# PCB.net
KiCad netlist of a schematic drawn in EAGLE
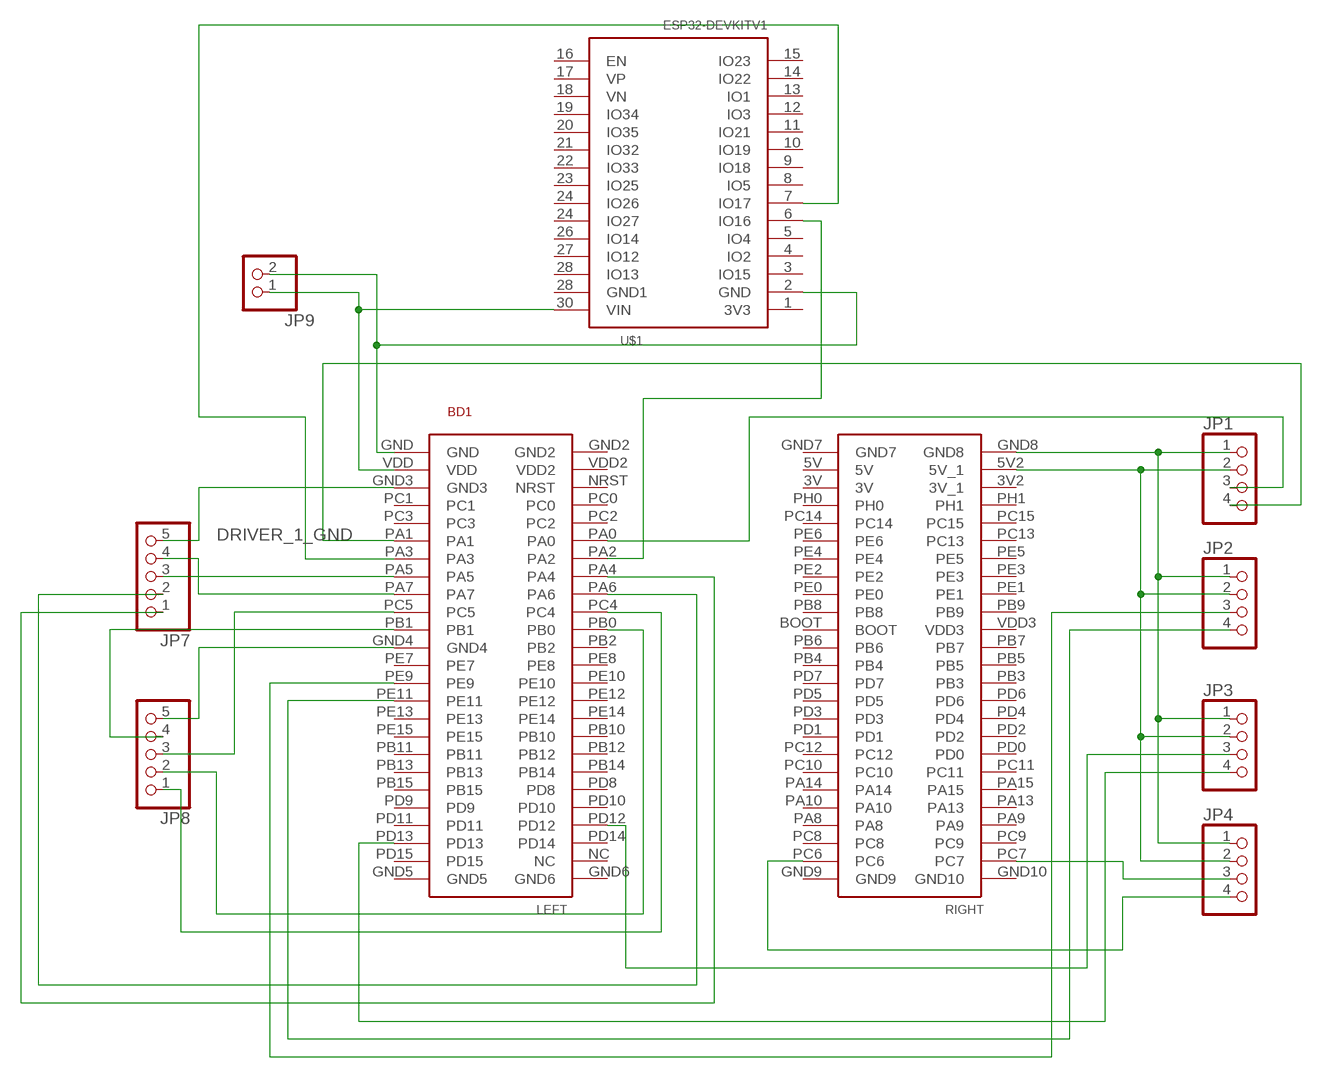
[diagram p0: schematic, sheet 1]

(export (version "E")
  (design (tool "Eeschema 10.0.6"))
  (components
    (comp (ref "BD1")
      (value "STM32F4-DISCOVERY")
      (footprint "eagle-import:STM32F407VG")
      (libsource (lib "eagle-import") (part "STM32F4-DISCOVERY"))
    )
    (comp (ref "JP1")
      (value "PINHD-1X4")
      (footprint "eagle-import:1X04")
      (libsource (lib "eagle-import") (part "PINHD-1X4"))
    )
    (comp (ref "JP2")
      (value "PINHD-1X4")
      (footprint "eagle-import:1X04")
      (libsource (lib "eagle-import") (part "PINHD-1X4"))
    )
    (comp (ref "JP3")
      (value "PINHD-1X4")
      (footprint "eagle-import:1X04")
      (libsource (lib "eagle-import") (part "PINHD-1X4"))
    )
    (comp (ref "JP4")
      (value "PINHD-1X4")
      (footprint "eagle-import:1X04")
      (libsource (lib "eagle-import") (part "PINHD-1X4"))
    )
    (comp (ref "JP7")
      (value "PINHD-1X5")
      (footprint "eagle-import:1X05")
      (libsource (lib "eagle-import") (part "PINHD-1X5"))
    )
    (comp (ref "JP8")
      (value "PINHD-1X5")
      (footprint "eagle-import:1X05")
      (libsource (lib "eagle-import") (part "PINHD-1X5"))
    )
    (comp (ref "JP9")
      (value "PINHD-1X2")
      (footprint "eagle-import:1X02")
      (libsource (lib "eagle-import") (part "PINHD-1X2"))
    )
    (comp (ref "U$1")
      (value "ESP32DEVKITV1")
      (footprint "eagle-import:ESP32-DEVKITV1")
      (libsource (lib "eagle-import") (part "ESP32DEVKITV1"))
    )
  )
  (nets
    (net (code "1") (name "/DRIVER_1_GND") (class "Default")
      (node (ref "BD1") (pin "GND3") (pinfunction "GND3_GND3") (pintype "bidirectional"))
      (node (ref "JP7") (pin "5") (pinfunction "5_5") (pintype "passive"))
    )
    (net (code "2") (name "Net-(BD1-5V_1)") (class "Default")
      (node (ref "BD1") (pin "5V2") (pinfunction "5V_1_5V2") (pintype "bidirectional"))
      (node (ref "JP1") (pin "2") (pinfunction "2_2") (pintype "passive"))
      (node (ref "JP2") (pin "2") (pinfunction "2_2") (pintype "passive"))
      (node (ref "JP3") (pin "2") (pinfunction "2_2") (pintype "passive"))
      (node (ref "JP4") (pin "2") (pinfunction "2_2") (pintype "passive"))
    )
    (net (code "3") (name "Net-(BD1-PadGND4)") (class "Default")
      (node (ref "BD1") (pin "GND4") (pinfunction "GND4_GND4") (pintype "bidirectional"))
      (node (ref "JP8") (pin "5") (pinfunction "5_5") (pintype "passive"))
    )
    (net (code "4") (name "Net-(BD1-PadGND8)") (class "Default")
      (node (ref "BD1") (pin "GND8") (pinfunction "GND8_GND8") (pintype "bidirectional"))
      (node (ref "JP1") (pin "1") (pinfunction "1_1") (pintype "passive"))
      (node (ref "JP2") (pin "1") (pinfunction "1_1") (pintype "passive"))
      (node (ref "JP3") (pin "1") (pinfunction "1_1") (pintype "passive"))
      (node (ref "JP4") (pin "1") (pinfunction "1_1") (pintype "passive"))
    )
    (net (code "5") (name "Net-(BD1-PadPA0)") (class "Default")
      (node (ref "BD1") (pin "PA0") (pinfunction "PA0_PA0") (pintype "bidirectional"))
      (node (ref "JP1") (pin "3") (pinfunction "3_3") (pintype "passive"))
    )
    (net (code "6") (name "Net-(BD1-PadPA1)") (class "Default")
      (node (ref "BD1") (pin "PA1") (pinfunction "PA1_PA1") (pintype "bidirectional"))
      (node (ref "JP1") (pin "4") (pinfunction "4_4") (pintype "passive"))
    )
    (net (code "7") (name "Net-(BD1-PadPA4)") (class "Default")
      (node (ref "BD1") (pin "PA4") (pinfunction "PA4_PA4") (pintype "bidirectional"))
      (node (ref "JP7") (pin "1") (pinfunction "1_1") (pintype "passive"))
    )
    (net (code "8") (name "Net-(BD1-PadPA5)") (class "Default")
      (node (ref "BD1") (pin "PA5") (pinfunction "PA5_PA5") (pintype "bidirectional"))
      (node (ref "JP7") (pin "3") (pinfunction "3_3") (pintype "passive"))
    )
    (net (code "9") (name "Net-(BD1-PadPA6)") (class "Default")
      (node (ref "BD1") (pin "PA6") (pinfunction "PA6_PA6") (pintype "bidirectional"))
      (node (ref "JP7") (pin "2") (pinfunction "2_2") (pintype "passive"))
    )
    (net (code "10") (name "Net-(BD1-PadPA7)") (class "Default")
      (node (ref "BD1") (pin "PA7") (pinfunction "PA7_PA7") (pintype "bidirectional"))
      (node (ref "JP7") (pin "4") (pinfunction "4_4") (pintype "passive"))
    )
    (net (code "11") (name "Net-(BD1-PadPB0)") (class "Default")
      (node (ref "BD1") (pin "PB0") (pinfunction "PB0_PB0") (pintype "bidirectional"))
      (node (ref "JP8") (pin "2") (pinfunction "2_2") (pintype "passive"))
    )
    (net (code "12") (name "Net-(BD1-PadPB1)") (class "Default")
      (node (ref "BD1") (pin "PB1") (pinfunction "PB1_PB1") (pintype "bidirectional"))
      (node (ref "JP8") (pin "4") (pinfunction "4_4") (pintype "passive"))
    )
    (net (code "13") (name "Net-(BD1-PadPC4)") (class "Default")
      (node (ref "BD1") (pin "PC4") (pinfunction "PC4_PC4") (pintype "bidirectional"))
      (node (ref "JP8") (pin "1") (pinfunction "1_1") (pintype "passive"))
    )
    (net (code "14") (name "Net-(BD1-PadPC5)") (class "Default")
      (node (ref "BD1") (pin "PC5") (pinfunction "PC5_PC5") (pintype "bidirectional"))
      (node (ref "JP8") (pin "3") (pinfunction "3_3") (pintype "passive"))
    )
    (net (code "15") (name "Net-(BD1-PadPC6)") (class "Default")
      (node (ref "BD1") (pin "PC6") (pinfunction "PC6_PC6") (pintype "bidirectional"))
      (node (ref "JP4") (pin "4") (pinfunction "4_4") (pintype "passive"))
    )
    (net (code "16") (name "Net-(BD1-PadPC7)") (class "Default")
      (node (ref "BD1") (pin "PC7") (pinfunction "PC7_PC7") (pintype "bidirectional"))
      (node (ref "JP4") (pin "3") (pinfunction "3_3") (pintype "passive"))
    )
    (net (code "17") (name "Net-(BD1-PadPD12)") (class "Default")
      (node (ref "BD1") (pin "PD12") (pinfunction "PD12_PD12") (pintype "bidirectional"))
      (node (ref "JP3") (pin "3") (pinfunction "3_3") (pintype "passive"))
    )
    (net (code "18") (name "Net-(BD1-PadPD13)") (class "Default")
      (node (ref "BD1") (pin "PD13") (pinfunction "PD13_PD13") (pintype "bidirectional"))
      (node (ref "JP3") (pin "4") (pinfunction "4_4") (pintype "passive"))
    )
    (net (code "19") (name "Net-(BD1-PadPE9)") (class "Default")
      (node (ref "BD1") (pin "PE9") (pinfunction "PE9_PE9") (pintype "bidirectional"))
      (node (ref "JP2") (pin "3") (pinfunction "3_3") (pintype "passive"))
    )
    (net (code "20") (name "Net-(BD1-PadPE11)") (class "Default")
      (node (ref "BD1") (pin "PE11") (pinfunction "PE11_PE11") (pintype "bidirectional"))
      (node (ref "JP2") (pin "4") (pinfunction "4_4") (pintype "passive"))
    )
    (net (code "21") (name "Net-(U$1-GND)") (class "Default")
      (node (ref "BD1") (pin "GND") (pinfunction "GND_GND") (pintype "bidirectional"))
      (node (ref "JP9") (pin "2") (pinfunction "2_2") (pintype "passive"))
      (node (ref "U$1") (pin "2") (pinfunction "GND_2") (pintype "bidirectional"))
    )
    (net (code "22") (name "Net-(U$1-IO16)") (class "Default")
      (node (ref "BD1") (pin "PA2") (pinfunction "PA2_PA2") (pintype "bidirectional"))
      (node (ref "U$1") (pin "6") (pinfunction "IO16_6") (pintype "bidirectional"))
    )
    (net (code "23") (name "Net-(U$1-IO17)") (class "Default")
      (node (ref "BD1") (pin "PA3") (pinfunction "PA3_PA3") (pintype "bidirectional"))
      (node (ref "U$1") (pin "7") (pinfunction "IO17_7") (pintype "bidirectional"))
    )
    (net (code "24") (name "Net-(U$1-VIN)") (class "Default")
      (node (ref "BD1") (pin "VDD") (pinfunction "VDD_VDD") (pintype "bidirectional"))
      (node (ref "JP9") (pin "1") (pinfunction "1_1") (pintype "passive"))
      (node (ref "U$1") (pin "30") (pinfunction "VIN_30") (pintype "bidirectional"))
    )
    (net (code "25") (name "unconnected-(BD1-3V_1-Pad3V2)") (class "Default")
      (node (ref "BD1") (pin "3V2") (pinfunction "3V_1_3V2") (pintype "bidirectional"))
    )
    (net (code "26") (name "unconnected-(BD1-Pad3V)") (class "Default")
      (node (ref "BD1") (pin "3V") (pinfunction "3V_3V") (pintype "bidirectional"))
    )
    (net (code "27") (name "unconnected-(BD1-Pad5V)") (class "Default")
      (node (ref "BD1") (pin "5V") (pinfunction "5V_5V") (pintype "bidirectional"))
    )
    (net (code "28") (name "unconnected-(BD1-PadBOOT)") (class "Default")
      (node (ref "BD1") (pin "BOOT") (pinfunction "BOOT_BOOT") (pintype "bidirectional"))
    )
    (net (code "29") (name "unconnected-(BD1-PadGND2)") (class "Default")
      (node (ref "BD1") (pin "GND2") (pinfunction "GND2_GND2") (pintype "bidirectional"))
    )
    (net (code "30") (name "unconnected-(BD1-PadGND5)") (class "Default")
      (node (ref "BD1") (pin "GND5") (pinfunction "GND5_GND5") (pintype "bidirectional"))
    )
    (net (code "31") (name "unconnected-(BD1-PadGND6)") (class "Default")
      (node (ref "BD1") (pin "GND6") (pinfunction "GND6_GND6") (pintype "bidirectional"))
    )
    (net (code "32") (name "unconnected-(BD1-PadGND7)") (class "Default")
      (node (ref "BD1") (pin "GND7") (pinfunction "GND7_GND7") (pintype "bidirectional"))
    )
    (net (code "33") (name "unconnected-(BD1-PadGND9)") (class "Default")
      (node (ref "BD1") (pin "GND9") (pinfunction "GND9_GND9") (pintype "bidirectional"))
    )
    (net (code "34") (name "unconnected-(BD1-PadGND10)") (class "Default")
      (node (ref "BD1") (pin "GND10") (pinfunction "GND10_GND10") (pintype "bidirectional"))
    )
    (net (code "35") (name "unconnected-(BD1-PadNC)") (class "Default")
      (node (ref "BD1") (pin "NC") (pinfunction "NC_NC") (pintype "bidirectional"))
    )
    (net (code "36") (name "unconnected-(BD1-PadNRST)") (class "Default")
      (node (ref "BD1") (pin "NRST") (pinfunction "NRST_NRST") (pintype "bidirectional"))
    )
    (net (code "37") (name "unconnected-(BD1-PadPA8)") (class "Default")
      (node (ref "BD1") (pin "PA8") (pinfunction "PA8_PA8") (pintype "bidirectional"))
    )
    (net (code "38") (name "unconnected-(BD1-PadPA9)") (class "Default")
      (node (ref "BD1") (pin "PA9") (pinfunction "PA9_PA9") (pintype "bidirectional"))
    )
    (net (code "39") (name "unconnected-(BD1-PadPA10)") (class "Default")
      (node (ref "BD1") (pin "PA10") (pinfunction "PA10_PA10") (pintype "bidirectional"))
    )
    (net (code "40") (name "unconnected-(BD1-PadPA13)") (class "Default")
      (node (ref "BD1") (pin "PA13") (pinfunction "PA13_PA13") (pintype "bidirectional"))
    )
    (net (code "41") (name "unconnected-(BD1-PadPA14)") (class "Default")
      (node (ref "BD1") (pin "PA14") (pinfunction "PA14_PA14") (pintype "bidirectional"))
    )
    (net (code "42") (name "unconnected-(BD1-PadPA15)") (class "Default")
      (node (ref "BD1") (pin "PA15") (pinfunction "PA15_PA15") (pintype "bidirectional"))
    )
    (net (code "43") (name "unconnected-(BD1-PadPB2)") (class "Default")
      (node (ref "BD1") (pin "PB2") (pinfunction "PB2_PB2") (pintype "bidirectional"))
    )
    (net (code "44") (name "unconnected-(BD1-PadPB3)") (class "Default")
      (node (ref "BD1") (pin "PB3") (pinfunction "PB3_PB3") (pintype "bidirectional"))
    )
    (net (code "45") (name "unconnected-(BD1-PadPB4)") (class "Default")
      (node (ref "BD1") (pin "PB4") (pinfunction "PB4_PB4") (pintype "bidirectional"))
    )
    (net (code "46") (name "unconnected-(BD1-PadPB5)") (class "Default")
      (node (ref "BD1") (pin "PB5") (pinfunction "PB5_PB5") (pintype "bidirectional"))
    )
    (net (code "47") (name "unconnected-(BD1-PadPB6)") (class "Default")
      (node (ref "BD1") (pin "PB6") (pinfunction "PB6_PB6") (pintype "bidirectional"))
    )
    (net (code "48") (name "unconnected-(BD1-PadPB7)") (class "Default")
      (node (ref "BD1") (pin "PB7") (pinfunction "PB7_PB7") (pintype "bidirectional"))
    )
    (net (code "49") (name "unconnected-(BD1-PadPB8)") (class "Default")
      (node (ref "BD1") (pin "PB8") (pinfunction "PB8_PB8") (pintype "bidirectional"))
    )
    (net (code "50") (name "unconnected-(BD1-PadPB9)") (class "Default")
      (node (ref "BD1") (pin "PB9") (pinfunction "PB9_PB9") (pintype "bidirectional"))
    )
    (net (code "51") (name "unconnected-(BD1-PadPB10)") (class "Default")
      (node (ref "BD1") (pin "PB10") (pinfunction "PB10_PB10") (pintype "bidirectional"))
    )
    (net (code "52") (name "unconnected-(BD1-PadPB11)") (class "Default")
      (node (ref "BD1") (pin "PB11") (pinfunction "PB11_PB11") (pintype "bidirectional"))
    )
    (net (code "53") (name "unconnected-(BD1-PadPB12)") (class "Default")
      (node (ref "BD1") (pin "PB12") (pinfunction "PB12_PB12") (pintype "bidirectional"))
    )
    (net (code "54") (name "unconnected-(BD1-PadPB13)") (class "Default")
      (node (ref "BD1") (pin "PB13") (pinfunction "PB13_PB13") (pintype "bidirectional"))
    )
    (net (code "55") (name "unconnected-(BD1-PadPB14)") (class "Default")
      (node (ref "BD1") (pin "PB14") (pinfunction "PB14_PB14") (pintype "bidirectional"))
    )
    (net (code "56") (name "unconnected-(BD1-PadPB15)") (class "Default")
      (node (ref "BD1") (pin "PB15") (pinfunction "PB15_PB15") (pintype "bidirectional"))
    )
    (net (code "57") (name "unconnected-(BD1-PadPC0)") (class "Default")
      (node (ref "BD1") (pin "PC0") (pinfunction "PC0_PC0") (pintype "bidirectional"))
    )
    (net (code "58") (name "unconnected-(BD1-PadPC1)") (class "Default")
      (node (ref "BD1") (pin "PC1") (pinfunction "PC1_PC1") (pintype "bidirectional"))
    )
    (net (code "59") (name "unconnected-(BD1-PadPC2)") (class "Default")
      (node (ref "BD1") (pin "PC2") (pinfunction "PC2_PC2") (pintype "bidirectional"))
    )
    (net (code "60") (name "unconnected-(BD1-PadPC3)") (class "Default")
      (node (ref "BD1") (pin "PC3") (pinfunction "PC3_PC3") (pintype "bidirectional"))
    )
    (net (code "61") (name "unconnected-(BD1-PadPC8)") (class "Default")
      (node (ref "BD1") (pin "PC8") (pinfunction "PC8_PC8") (pintype "bidirectional"))
    )
    (net (code "62") (name "unconnected-(BD1-PadPC9)") (class "Default")
      (node (ref "BD1") (pin "PC9") (pinfunction "PC9_PC9") (pintype "bidirectional"))
    )
    (net (code "63") (name "unconnected-(BD1-PadPC10)") (class "Default")
      (node (ref "BD1") (pin "PC10") (pinfunction "PC10_PC10") (pintype "bidirectional"))
    )
    (net (code "64") (name "unconnected-(BD1-PadPC11)") (class "Default")
      (node (ref "BD1") (pin "PC11") (pinfunction "PC11_PC11") (pintype "bidirectional"))
    )
    (net (code "65") (name "unconnected-(BD1-PadPC12)") (class "Default")
      (node (ref "BD1") (pin "PC12") (pinfunction "PC12_PC12") (pintype "bidirectional"))
    )
    (net (code "66") (name "unconnected-(BD1-PadPC13)") (class "Default")
      (node (ref "BD1") (pin "PC13") (pinfunction "PC13_PC13") (pintype "bidirectional"))
    )
    (net (code "67") (name "unconnected-(BD1-PadPC14)") (class "Default")
      (node (ref "BD1") (pin "PC14") (pinfunction "PC14_PC14") (pintype "bidirectional"))
    )
    (net (code "68") (name "unconnected-(BD1-PadPC15)") (class "Default")
      (node (ref "BD1") (pin "PC15") (pinfunction "PC15_PC15") (pintype "bidirectional"))
    )
    (net (code "69") (name "unconnected-(BD1-PadPD0)") (class "Default")
      (node (ref "BD1") (pin "PD0") (pinfunction "PD0_PD0") (pintype "bidirectional"))
    )
    (net (code "70") (name "unconnected-(BD1-PadPD1)") (class "Default")
      (node (ref "BD1") (pin "PD1") (pinfunction "PD1_PD1") (pintype "bidirectional"))
    )
    (net (code "71") (name "unconnected-(BD1-PadPD2)") (class "Default")
      (node (ref "BD1") (pin "PD2") (pinfunction "PD2_PD2") (pintype "bidirectional"))
    )
    (net (code "72") (name "unconnected-(BD1-PadPD3)") (class "Default")
      (node (ref "BD1") (pin "PD3") (pinfunction "PD3_PD3") (pintype "bidirectional"))
    )
    (net (code "73") (name "unconnected-(BD1-PadPD4)") (class "Default")
      (node (ref "BD1") (pin "PD4") (pinfunction "PD4_PD4") (pintype "bidirectional"))
    )
    (net (code "74") (name "unconnected-(BD1-PadPD5)") (class "Default")
      (node (ref "BD1") (pin "PD5") (pinfunction "PD5_PD5") (pintype "bidirectional"))
    )
    (net (code "75") (name "unconnected-(BD1-PadPD6)") (class "Default")
      (node (ref "BD1") (pin "PD6") (pinfunction "PD6_PD6") (pintype "bidirectional"))
    )
    (net (code "76") (name "unconnected-(BD1-PadPD7)") (class "Default")
      (node (ref "BD1") (pin "PD7") (pinfunction "PD7_PD7") (pintype "bidirectional"))
    )
    (net (code "77") (name "unconnected-(BD1-PadPD8)") (class "Default")
      (node (ref "BD1") (pin "PD8") (pinfunction "PD8_PD8") (pintype "bidirectional"))
    )
    (net (code "78") (name "unconnected-(BD1-PadPD9)") (class "Default")
      (node (ref "BD1") (pin "PD9") (pinfunction "PD9_PD9") (pintype "bidirectional"))
    )
    (net (code "79") (name "unconnected-(BD1-PadPD10)") (class "Default")
      (node (ref "BD1") (pin "PD10") (pinfunction "PD10_PD10") (pintype "bidirectional"))
    )
    (net (code "80") (name "unconnected-(BD1-PadPD11)") (class "Default")
      (node (ref "BD1") (pin "PD11") (pinfunction "PD11_PD11") (pintype "bidirectional"))
    )
    (net (code "81") (name "unconnected-(BD1-PadPD14)") (class "Default")
      (node (ref "BD1") (pin "PD14") (pinfunction "PD14_PD14") (pintype "bidirectional"))
    )
    (net (code "82") (name "unconnected-(BD1-PadPD15)") (class "Default")
      (node (ref "BD1") (pin "PD15") (pinfunction "PD15_PD15") (pintype "bidirectional"))
    )
    (net (code "83") (name "unconnected-(BD1-PadPE0)") (class "Default")
      (node (ref "BD1") (pin "PE0") (pinfunction "PE0_PE0") (pintype "bidirectional"))
    )
    (net (code "84") (name "unconnected-(BD1-PadPE1)") (class "Default")
      (node (ref "BD1") (pin "PE1") (pinfunction "PE1_PE1") (pintype "bidirectional"))
    )
    (net (code "85") (name "unconnected-(BD1-PadPE2)") (class "Default")
      (node (ref "BD1") (pin "PE2") (pinfunction "PE2_PE2") (pintype "bidirectional"))
    )
    (net (code "86") (name "unconnected-(BD1-PadPE3)") (class "Default")
      (node (ref "BD1") (pin "PE3") (pinfunction "PE3_PE3") (pintype "bidirectional"))
    )
    (net (code "87") (name "unconnected-(BD1-PadPE4)") (class "Default")
      (node (ref "BD1") (pin "PE4") (pinfunction "PE4_PE4") (pintype "bidirectional"))
    )
    (net (code "88") (name "unconnected-(BD1-PadPE5)") (class "Default")
      (node (ref "BD1") (pin "PE5") (pinfunction "PE5_PE5") (pintype "bidirectional"))
    )
    (net (code "89") (name "unconnected-(BD1-PadPE6)") (class "Default")
      (node (ref "BD1") (pin "PE6") (pinfunction "PE6_PE6") (pintype "bidirectional"))
    )
    (net (code "90") (name "unconnected-(BD1-PadPE7)") (class "Default")
      (node (ref "BD1") (pin "PE7") (pinfunction "PE7_PE7") (pintype "bidirectional"))
    )
    (net (code "91") (name "unconnected-(BD1-PadPE8)") (class "Default")
      (node (ref "BD1") (pin "PE8") (pinfunction "PE8_PE8") (pintype "bidirectional"))
    )
    (net (code "92") (name "unconnected-(BD1-PadPE10)") (class "Default")
      (node (ref "BD1") (pin "PE10") (pinfunction "PE10_PE10") (pintype "bidirectional"))
    )
    (net (code "93") (name "unconnected-(BD1-PadPE12)") (class "Default")
      (node (ref "BD1") (pin "PE12") (pinfunction "PE12_PE12") (pintype "bidirectional"))
    )
    (net (code "94") (name "unconnected-(BD1-PadPE13)") (class "Default")
      (node (ref "BD1") (pin "PE13") (pinfunction "PE13_PE13") (pintype "bidirectional"))
    )
    (net (code "95") (name "unconnected-(BD1-PadPE14)") (class "Default")
      (node (ref "BD1") (pin "PE14") (pinfunction "PE14_PE14") (pintype "bidirectional"))
    )
    (net (code "96") (name "unconnected-(BD1-PadPE15)") (class "Default")
      (node (ref "BD1") (pin "PE15") (pinfunction "PE15_PE15") (pintype "bidirectional"))
    )
    (net (code "97") (name "unconnected-(BD1-PadPH0)") (class "Default")
      (node (ref "BD1") (pin "PH0") (pinfunction "PH0_PH0") (pintype "bidirectional"))
    )
    (net (code "98") (name "unconnected-(BD1-PadPH1)") (class "Default")
      (node (ref "BD1") (pin "PH1") (pinfunction "PH1_PH1") (pintype "bidirectional"))
    )
    (net (code "99") (name "unconnected-(BD1-PadVDD2)") (class "Default")
      (node (ref "BD1") (pin "VDD2") (pinfunction "VDD2_VDD2") (pintype "bidirectional"))
    )
    (net (code "100") (name "unconnected-(BD1-PadVDD3)") (class "Default")
      (node (ref "BD1") (pin "VDD3") (pinfunction "VDD3_VDD3") (pintype "bidirectional"))
    )
    (net (code "101") (name "unconnected-(U$1-3V3-Pad1)") (class "Default")
      (node (ref "U$1") (pin "1") (pinfunction "3V3_1") (pintype "bidirectional"))
    )
    (net (code "102") (name "unconnected-(U$1-EN-Pad16)") (class "Default")
      (node (ref "U$1") (pin "16") (pinfunction "EN_16") (pintype "bidirectional"))
    )
    (net (code "103") (name "unconnected-(U$1-GND1-Pad28)") (class "Default")
      (node (ref "U$1") (pin "28") (pinfunction "GND1_28") (pintype "bidirectional"))
    )
    (net (code "104") (name "unconnected-(U$1-IO1-Pad13)") (class "Default")
      (node (ref "U$1") (pin "13") (pinfunction "IO1_13") (pintype "bidirectional"))
    )
    (net (code "105") (name "unconnected-(U$1-IO2-Pad4)") (class "Default")
      (node (ref "U$1") (pin "4") (pinfunction "IO2_4") (pintype "bidirectional"))
    )
    (net (code "106") (name "unconnected-(U$1-IO3-Pad12)") (class "Default")
      (node (ref "U$1") (pin "12") (pinfunction "IO3_12") (pintype "bidirectional"))
    )
    (net (code "107") (name "unconnected-(U$1-IO4-Pad5)") (class "Default")
      (node (ref "U$1") (pin "5") (pinfunction "IO4_5") (pintype "bidirectional"))
    )
    (net (code "108") (name "unconnected-(U$1-IO5-Pad8)") (class "Default")
      (node (ref "U$1") (pin "8") (pinfunction "IO5_8") (pintype "bidirectional"))
    )
    (net (code "109") (name "unconnected-(U$1-IO12-Pad27)") (class "Default")
      (node (ref "U$1") (pin "27") (pinfunction "IO12_27") (pintype "bidirectional"))
    )
    (net (code "110") (name "unconnected-(U$1-IO13-Pad28)") (class "Default")
      (node (ref "U$1") (pin "28") (pinfunction "IO13_28") (pintype "bidirectional"))
    )
    (net (code "111") (name "unconnected-(U$1-IO14-Pad26)") (class "Default")
      (node (ref "U$1") (pin "26") (pinfunction "IO14_26") (pintype "bidirectional"))
    )
    (net (code "112") (name "unconnected-(U$1-IO15-Pad3)") (class "Default")
      (node (ref "U$1") (pin "3") (pinfunction "IO15_3") (pintype "bidirectional"))
    )
    (net (code "113") (name "unconnected-(U$1-IO18-Pad9)") (class "Default")
      (node (ref "U$1") (pin "9") (pinfunction "IO18_9") (pintype "bidirectional"))
    )
    (net (code "114") (name "unconnected-(U$1-IO19-Pad10)") (class "Default")
      (node (ref "U$1") (pin "10") (pinfunction "IO19_10") (pintype "bidirectional"))
    )
    (net (code "115") (name "unconnected-(U$1-IO21-Pad11)") (class "Default")
      (node (ref "U$1") (pin "11") (pinfunction "IO21_11") (pintype "bidirectional"))
    )
    (net (code "116") (name "unconnected-(U$1-IO22-Pad14)") (class "Default")
      (node (ref "U$1") (pin "14") (pinfunction "IO22_14") (pintype "bidirectional"))
    )
    (net (code "117") (name "unconnected-(U$1-IO23-Pad15)") (class "Default")
      (node (ref "U$1") (pin "15") (pinfunction "IO23_15") (pintype "bidirectional"))
    )
    (net (code "118") (name "unconnected-(U$1-IO25-Pad23)") (class "Default")
      (node (ref "U$1") (pin "23") (pinfunction "IO25_23") (pintype "bidirectional"))
    )
    (net (code "119") (name "unconnected-(U$1-IO26-Pad24)") (class "Default")
      (node (ref "U$1") (pin "24") (pinfunction "IO26_24") (pintype "bidirectional"))
    )
    (net (code "120") (name "unconnected-(U$1-IO27-Pad24)") (class "Default")
      (node (ref "U$1") (pin "24") (pinfunction "IO27_24") (pintype "bidirectional"))
    )
    (net (code "121") (name "unconnected-(U$1-IO32-Pad21)") (class "Default")
      (node (ref "U$1") (pin "21") (pinfunction "IO32_21") (pintype "bidirectional"))
    )
    (net (code "122") (name "unconnected-(U$1-IO33-Pad22)") (class "Default")
      (node (ref "U$1") (pin "22") (pinfunction "IO33_22") (pintype "bidirectional"))
    )
    (net (code "123") (name "unconnected-(U$1-IO34-Pad19)") (class "Default")
      (node (ref "U$1") (pin "19") (pinfunction "IO34_19") (pintype "bidirectional"))
    )
    (net (code "124") (name "unconnected-(U$1-IO35-Pad20)") (class "Default")
      (node (ref "U$1") (pin "20") (pinfunction "IO35_20") (pintype "bidirectional"))
    )
    (net (code "125") (name "unconnected-(U$1-VN-Pad18)") (class "Default")
      (node (ref "U$1") (pin "18") (pinfunction "VN_18") (pintype "bidirectional"))
    )
    (net (code "126") (name "unconnected-(U$1-VP-Pad17)") (class "Default")
      (node (ref "U$1") (pin "17") (pinfunction "VP_17") (pintype "bidirectional"))
    )
  )
)
